# 5-DisplayPort_Ethernet.net
KiCad netlist of a schematic drawn in Altium Designer
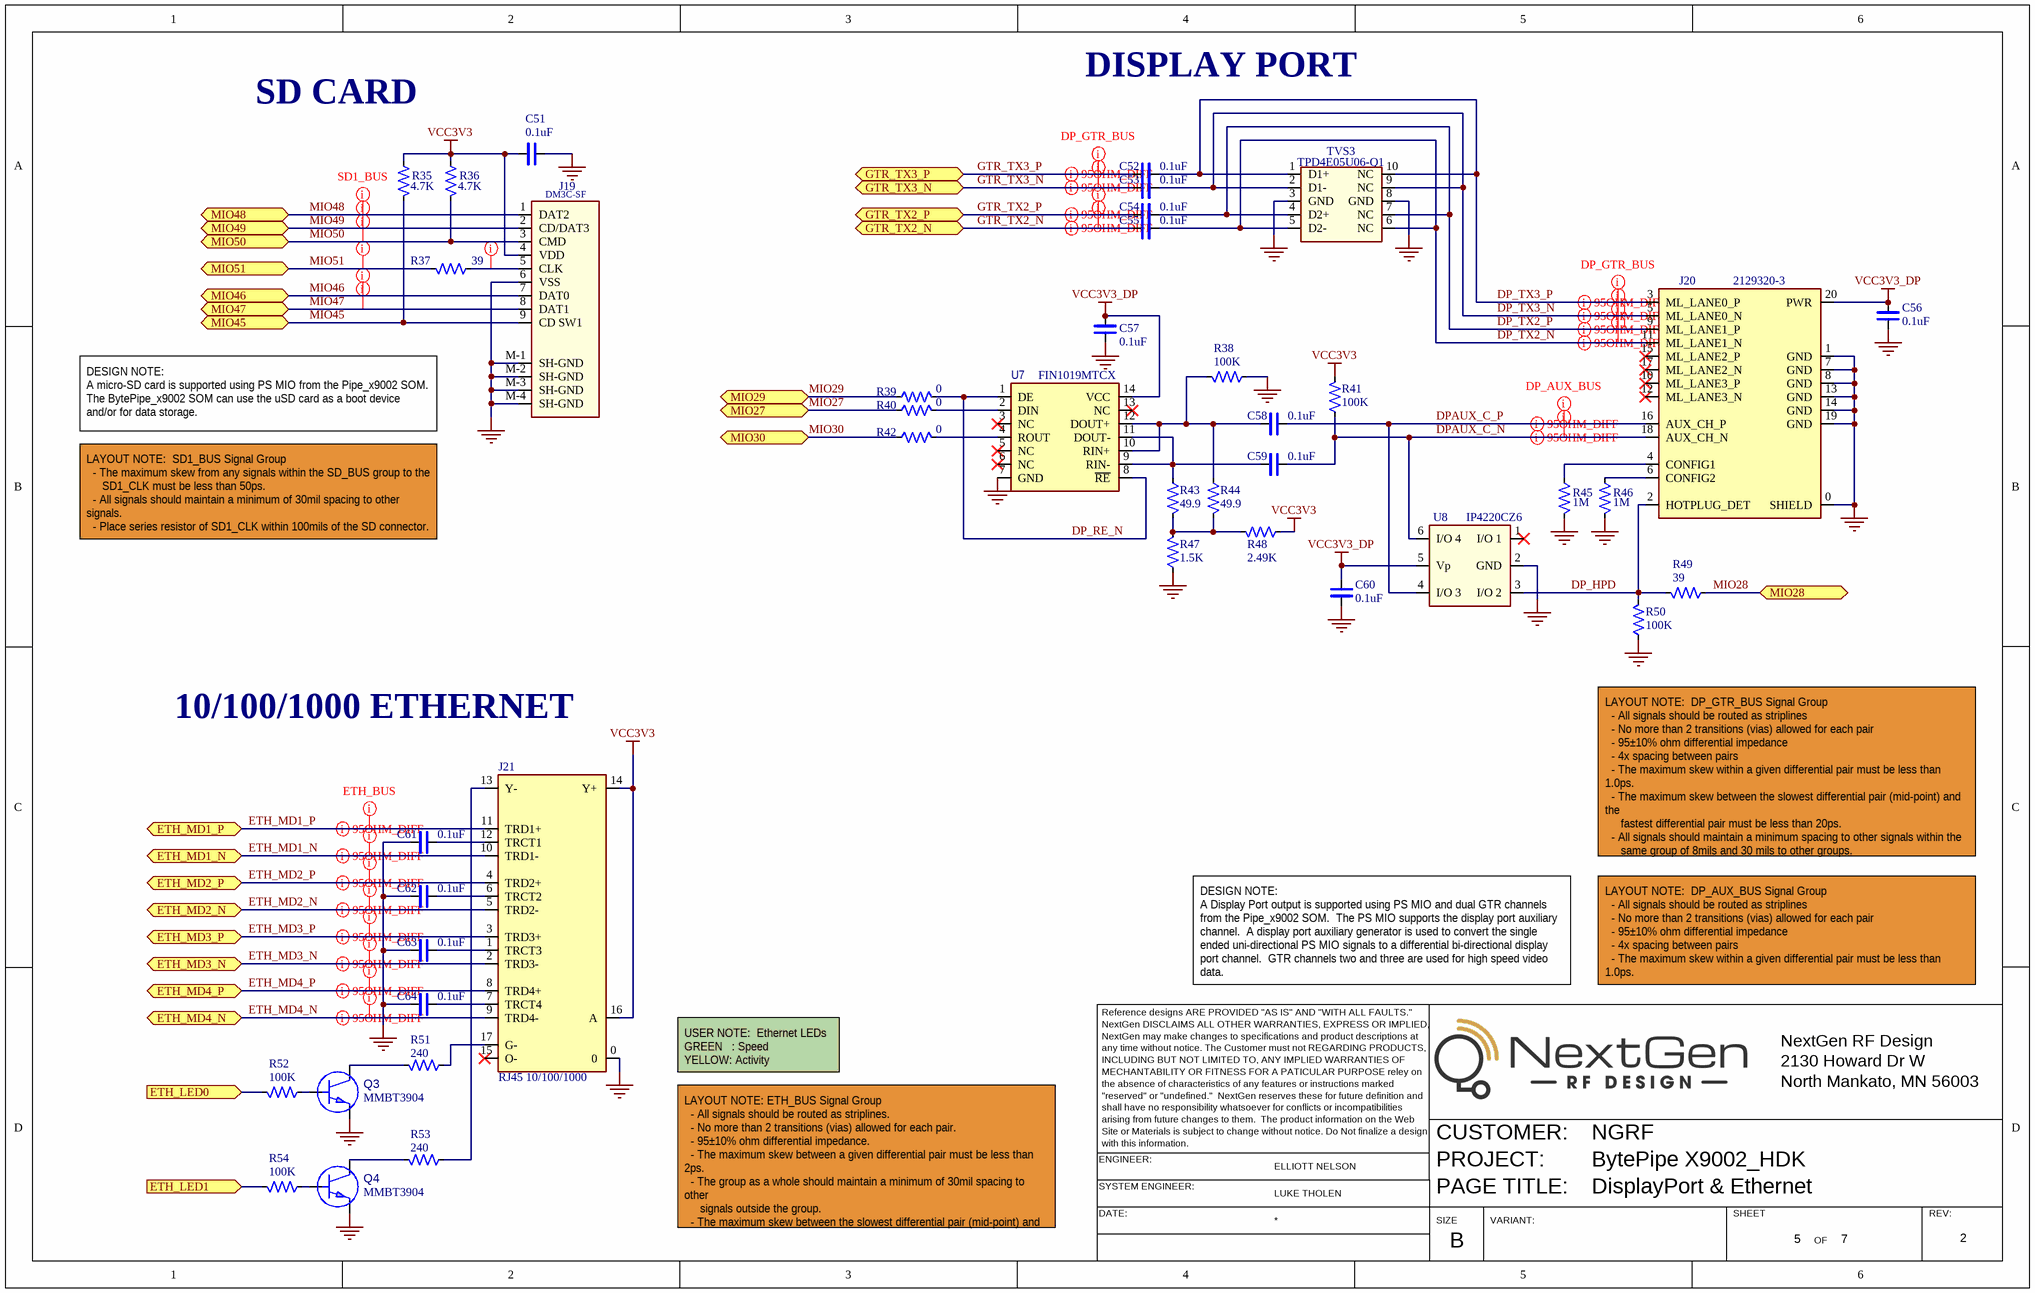
[diagram p0: 5-DisplayPort & Ethernet.SchDoc]

(export (version "E")
  (design (tool "Eeschema 10.0.6"))
  (components
    (comp (ref "C51")
      (value "0.1uF")
      (footprint "SM/0402/CAP")
      (description "CAP CER 0.1UF 25V X7R 0402")
      (fields (field (name "Comment") "CAP_CERAMIC_0402"))
      (libsource (lib "NextGenRF_Symbols_SMT") (part "CAP_CERAMIC_0402"))
    )
    (comp (ref "C52")
      (value "0.1uF")
      (footprint "SM/0402/CAP")
      (description "CAP CER 0.1UF 25V X7R 0402")
      (fields (field (name "Comment") "CAP_CERAMIC_0402"))
      (libsource (lib "NextGenRF_Symbols_SMT") (part "CAP_CERAMIC_0402"))
    )
    (comp (ref "C53")
      (value "0.1uF")
      (footprint "SM/0402/CAP")
      (description "CAP CER 0.1UF 25V X7R 0402")
      (fields (field (name "Comment") "CAP_CERAMIC_0402"))
      (libsource (lib "NextGenRF_Symbols_SMT") (part "CAP_CERAMIC_0402"))
    )
    (comp (ref "C54")
      (value "0.1uF")
      (footprint "SM/0402/CAP")
      (description "CAP CER 0.1UF 25V X7R 0402")
      (fields (field (name "Comment") "CAP_CERAMIC_0402"))
      (libsource (lib "NextGenRF_Symbols_SMT") (part "CAP_CERAMIC_0402"))
    )
    (comp (ref "C55")
      (value "0.1uF")
      (footprint "SM/0402/CAP")
      (description "CAP CER 0.1UF 25V X7R 0402")
      (fields (field (name "Comment") "CAP_CERAMIC_0402"))
      (libsource (lib "NextGenRF_Symbols_SMT") (part "CAP_CERAMIC_0402"))
    )
    (comp (ref "C56")
      (value "0.1uF")
      (footprint "SM/0402/CAP")
      (description "CAP CER 0.1UF 25V X7R 0402")
      (fields (field (name "Comment") "CAP_CERAMIC_0402"))
      (libsource (lib "NextGenRF_Symbols_SMT") (part "CAP_CERAMIC_0402"))
    )
    (comp (ref "C57")
      (value "0.1uF")
      (footprint "SM/0402/CAP")
      (description "CAP CER 0.1UF 25V X7R 0402")
      (fields (field (name "Comment") "CAP_CERAMIC_0402"))
      (libsource (lib "NextGenRF_Symbols_SMT") (part "CAP_CERAMIC_0402"))
    )
    (comp (ref "C58")
      (value "0.1uF")
      (footprint "SM/0402/CAP")
      (description "CAP CER 0.1UF 25V X7R 0402")
      (fields (field (name "Comment") "CAP_CERAMIC_0402"))
      (libsource (lib "NextGenRF_Symbols_SMT") (part "CAP_CERAMIC_0402"))
    )
    (comp (ref "C59")
      (value "0.1uF")
      (footprint "SM/0402/CAP")
      (description "CAP CER 0.1UF 25V X7R 0402")
      (fields (field (name "Comment") "CAP_CERAMIC_0402"))
      (libsource (lib "NextGenRF_Symbols_SMT") (part "CAP_CERAMIC_0402"))
    )
    (comp (ref "C60")
      (value "0.1uF")
      (footprint "SM/0402/CAP")
      (description "CAP CER 0.1UF 25V X7R 0402")
      (fields (field (name "Comment") "CAP_CERAMIC_0402"))
      (libsource (lib "NextGenRF_Symbols_SMT") (part "CAP_CERAMIC_0402"))
    )
    (comp (ref "C61")
      (value "0.1uF")
      (footprint "SM/0402/CAP")
      (description "CAP CER 0.1UF 25V X7R 0402")
      (fields (field (name "Comment") "CAP_CERAMIC_0402"))
      (libsource (lib "NextGenRF_Symbols_SMT") (part "CAP_CERAMIC_0402"))
    )
    (comp (ref "C62")
      (value "0.1uF")
      (footprint "SM/0402/CAP")
      (description "CAP CER 0.1UF 25V X7R 0402")
      (fields (field (name "Comment") "CAP_CERAMIC_0402"))
      (libsource (lib "NextGenRF_Symbols_SMT") (part "CAP_CERAMIC_0402"))
    )
    (comp (ref "C63")
      (value "0.1uF")
      (footprint "SM/0402/CAP")
      (description "CAP CER 0.1UF 25V X7R 0402")
      (fields (field (name "Comment") "CAP_CERAMIC_0402"))
      (libsource (lib "NextGenRF_Symbols_SMT") (part "CAP_CERAMIC_0402"))
    )
    (comp (ref "C64")
      (value "0.1uF")
      (footprint "SM/0402/CAP")
      (description "CAP CER 0.1UF 25V X7R 0402")
      (fields (field (name "Comment") "CAP_CERAMIC_0402"))
      (libsource (lib "NextGenRF_Symbols_SMT") (part "CAP_CERAMIC_0402"))
    )
    (comp (ref "J19")
      (value "DM3C-SF")
      (footprint "SM/CON/MICRO_SD-CARD/HOLDER")
      (description "10 (8 + 2) Position Card Connector Secure Digital - microSD™ Surface Mount, Right Angle Gold")
      (fields (field (name "Comment") "CONN MICRO SD CARD HINGED TYPE"))
      (libsource (lib "NextGenRF_Symbols_SMT") (part "CON_HIROSE_MICRO-SD_HINGED"))
    )
    (comp (ref "J20")
      (value "2129320-3")
      (footprint "CON/TE/2129320-3")
      (description "DisplayPort, Mini  Receptacle Connector 20 Position Through Hole, Right Angle..")
      (fields (field (name "Comment") "CON_TE_2129320-3"))
      (libsource (lib "NextGenRF_Symbols_TH") (part "CON_TE_2129320-3"))
    )
    (comp (ref "J21")
      (value "RJ45 10/100/1000")
      (footprint "CON/RJ45/L829-1J1T-43")
      (description "1 Port RJ45 Magjack Connector Through Hole 10/100/1000 Base-T, AutoMDIX")
      (fields (field (name "Comment") "CON_RJ45_MagJack_L829-1J1T-43"))
      (libsource (lib "NextGenRF_Symbols_TH") (part "CON_RJ45_MagJack_L829-1J1T-43"))
    )
    (comp (ref "Q3")
      (value "MMBT3904")
      (footprint "NGRF_SMT_Footprints:SM/SOT23_A")
      (description "Bipolar (BJT) Transistor NPN 40V 200mA 300MHz 300mW Surface Mount SOT-23-3 (TO-236)")
      (fields (field (name "Comment") "TRANSISTOR_NPN_SOT23"))
      (libsource (lib "NextGenRF_Symbols_SMT") (part "TRANSISTOR_NPN_SOT23"))
    )
    (comp (ref "Q4")
      (value "MMBT3904")
      (footprint "NGRF_SMT_Footprints:SM/SOT23_A")
      (description "Bipolar (BJT) Transistor NPN 40V 200mA 300MHz 300mW Surface Mount SOT-23-3 (TO-236)")
      (fields (field (name "Comment") "TRANSISTOR_NPN_SOT23"))
      (libsource (lib "NextGenRF_Symbols_SMT") (part "TRANSISTOR_NPN_SOT23"))
    )
    (comp (ref "R35")
      (value "4.7K")
      (footprint "SM/0402/RES")
      (description "RES SMD 4.7K OHM 1% 1/10W 0402")
      (fields (field (name "Comment") "RES_0402_A"))
      (libsource (lib "NextGenRF_Symbols_SMT") (part "RES_0402_A"))
    )
    (comp (ref "R36")
      (value "4.7K")
      (footprint "SM/0402/RES")
      (description "RES SMD 4.7K OHM 1% 1/10W 0402")
      (fields (field (name "Comment") "RES_0402_A"))
      (libsource (lib "NextGenRF_Symbols_SMT") (part "RES_0402_A"))
    )
    (comp (ref "R37")
      (value "39")
      (footprint "SM/0402/RES")
      (description "RES SMD 39 OHM 1% 1/10W 0402")
      (fields (field (name "Comment") "RES_0402_A"))
      (libsource (lib "NextGenRF_Symbols_SMT") (part "RES_0402_A"))
    )
    (comp (ref "R38")
      (value "100K")
      (footprint "SM/0402/RES")
      (description "RES SMD 100K OHM 1% 1/10W 0402")
      (fields (field (name "Comment") "RES_0402_A"))
      (libsource (lib "NextGenRF_Symbols_SMT") (part "RES_0402_A"))
    )
    (comp (ref "R39")
      (value "0")
      (footprint "SM/0402/RES")
      (description "RES SMD 0 OHM JUMPER 1/10W 0402")
      (fields (field (name "Comment") "RES_0402_A"))
      (libsource (lib "NextGenRF_Symbols_SMT") (part "RES_0402_A"))
    )
    (comp (ref "R40")
      (value "0")
      (footprint "SM/0402/RES")
      (description "RES SMD 0 OHM JUMPER 1/10W 0402")
      (fields (field (name "Comment") "RES_0402_A"))
      (libsource (lib "NextGenRF_Symbols_SMT") (part "RES_0402_A"))
    )
    (comp (ref "R41")
      (value "100K")
      (footprint "SM/0402/RES")
      (description "RES SMD 100K OHM 1% 1/10W 0402")
      (fields (field (name "Comment") "RES_0402_A"))
      (libsource (lib "NextGenRF_Symbols_SMT") (part "RES_0402_A"))
    )
    (comp (ref "R42")
      (value "0")
      (footprint "SM/0402/RES")
      (description "RES SMD 0 OHM JUMPER 1/10W 0402")
      (fields (field (name "Comment") "RES_0402_A"))
      (libsource (lib "NextGenRF_Symbols_SMT") (part "RES_0402_A"))
    )
    (comp (ref "R43")
      (value "49.9")
      (footprint "SM/0402/RES")
      (description "RES 49.9 OHM 1% 1/10W 0402")
      (fields (field (name "Comment") "RES_0402_A"))
      (libsource (lib "NextGenRF_Symbols_SMT") (part "RES_0402_A"))
    )
    (comp (ref "R44")
      (value "49.9")
      (footprint "SM/0402/RES")
      (description "RES 49.9 OHM 1% 1/10W 0402")
      (fields (field (name "Comment") "RES_0402_A"))
      (libsource (lib "NextGenRF_Symbols_SMT") (part "RES_0402_A"))
    )
    (comp (ref "R45")
      (value "1M")
      (footprint "SM/0402/RES")
      (description "RES SMD 1M OHM 1% 1/10W 0402")
      (fields (field (name "Comment") "RES_0402_A"))
      (libsource (lib "NextGenRF_Symbols_SMT") (part "RES_0402_A"))
    )
    (comp (ref "R46")
      (value "1M")
      (footprint "SM/0402/RES")
      (description "RES SMD 1M OHM 1% 1/10W 0402")
      (fields (field (name "Comment") "RES_0402_A"))
      (libsource (lib "NextGenRF_Symbols_SMT") (part "RES_0402_A"))
    )
    (comp (ref "R47")
      (value "1.5K")
      (footprint "SM/0402/RES")
      (description "RES SMD 1.5K OHM 1% 1/10W 0402")
      (fields (field (name "Comment") "RES_0402_A"))
      (libsource (lib "NextGenRF_Symbols_SMT") (part "RES_0402_A"))
    )
    (comp (ref "R48")
      (value "2.49K")
      (footprint "SM/0402/RES")
      (description "RES SMD 2.49K OHM 1% 1/10W 0402")
      (fields (field (name "Comment") "RES_0402_A"))
      (libsource (lib "NextGenRF_Symbols_SMT") (part "RES_0402_A"))
    )
    (comp (ref "R49")
      (value "39")
      (footprint "SM/0402/RES")
      (description "RES SMD 39 OHM 1% 1/10W 0402")
      (fields (field (name "Comment") "RES_0402_A"))
      (libsource (lib "NextGenRF_Symbols_SMT") (part "RES_0402_A"))
    )
    (comp (ref "R50")
      (value "100K")
      (footprint "SM/0402/RES")
      (description "RES SMD 100K OHM 1% 1/10W 0402")
      (fields (field (name "Comment") "RES_0402_A"))
      (libsource (lib "NextGenRF_Symbols_SMT") (part "RES_0402_A"))
    )
    (comp (ref "R51")
      (value "240")
      (footprint "SM/0402/RES")
      (description "RES SMD 240 OHM 1% 1/10W 0402")
      (fields (field (name "Comment") "RES_0402_A"))
      (libsource (lib "NextGenRF_Symbols_SMT") (part "RES_0402_A"))
    )
    (comp (ref "R52")
      (value "100K")
      (footprint "SM/0402/RES")
      (description "RES SMD 100K OHM 1% 1/10W 0402")
      (fields (field (name "Comment") "RES_0402_A"))
      (libsource (lib "NextGenRF_Symbols_SMT") (part "RES_0402_A"))
    )
    (comp (ref "R53")
      (value "240")
      (footprint "SM/0402/RES")
      (description "RES SMD 240 OHM 1% 1/10W 0402")
      (fields (field (name "Comment") "RES_0402_A"))
      (libsource (lib "NextGenRF_Symbols_SMT") (part "RES_0402_A"))
    )
    (comp (ref "R54")
      (value "100K")
      (footprint "SM/0402/RES")
      (description "RES SMD 100K OHM 1% 1/10W 0402")
      (fields (field (name "Comment") "RES_0402_A"))
      (libsource (lib "NextGenRF_Symbols_SMT") (part "RES_0402_A"))
    )
    (comp (ref "TVS3")
      (value "TPD4E05U06-Q1")
      (footprint "SM/DFN10/2.5X1MM_A")
      (description "TVS DIODE 5.5V 14V 10SON")
      (fields (field (name "Comment") "TVS_TPD4E05U06_2.5mmX1mm"))
      (libsource (lib "NextGenRF_Symbols_SMT") (part "TVS_TPD4E05U06_2.5mmX1mm"))
    )
    (comp (ref "U7")
      (value "FIN1019MTCX")
      (footprint "SM/TSSOP14_5X6.4MM_A")
      (description "1/1 Transceiver Full LVDS 14-TSSOP")
      (fields (field (name "Comment") "IC_FIN1019MTCX_TSSOP-14"))
      (libsource (lib "NextGenRF_Symbols_SMT") (part "IC_FIN1019MTCX_TSSOP-14"))
    )
    (comp (ref "U8")
      (value "IP4220CZ6")
      (footprint "SM/TSOP-6_A")
      (description "Dual USB ESD Protection")
      (fields (field (name "Comment") "IC_IP4220CZ6_TSOP-6"))
      (libsource (lib "NextGenRF_Symbols_SMT") (part "IC_IP4220CZ6_TSOP-6"))
    )
  )
  (nets
    (net (code "1") (name "/DPAUX_C_N") (class "Default")
      (node (ref "C59") (pin "2") (pinfunction "N2_2") (pintype "passive"))
      (node (ref "J20") (pin "18") (pinfunction "AUX_CH_N_18") (pintype "passive"))
      (node (ref "R41") (pin "1") (pinfunction "1_1") (pintype "passive"))
      (node (ref "U8") (pin "6") (pinfunction "I/O_4_6") (pintype "passive"))
    )
    (net (code "2") (name "/DPAUX_C_P") (class "Default")
      (node (ref "C58") (pin "2") (pinfunction "N2_2") (pintype "passive"))
      (node (ref "J20") (pin "16") (pinfunction "AUX_CH_P_16") (pintype "passive"))
      (node (ref "U8") (pin "4") (pinfunction "I/O_3_4") (pintype "passive"))
    )
    (net (code "3") (name "/DP_HPD") (class "Default")
      (node (ref "J20") (pin "2") (pinfunction "HOTPLUG_DET_2") (pintype "passive"))
      (node (ref "R49") (pin "2") (pinfunction "2_2") (pintype "passive"))
      (node (ref "R50") (pin "2") (pinfunction "2_2") (pintype "passive"))
      (node (ref "U8") (pin "3") (pinfunction "I/O_2_3") (pintype "passive"))
    )
    (net (code "4") (name "/DP_RE_N") (class "Default")
      (node (ref "R39") (pin "1") (pinfunction "1_1") (pintype "passive"))
      (node (ref "U7") (pin "1") (pinfunction "DE_1") (pintype "passive"))
      (node (ref "U7") (pin "8") (pinfunction "~{RE}_8") (pintype "passive"))
    )
    (net (code "5") (name "/DP_TX2_N") (class "Default")
      (node (ref "C55") (pin "2") (pinfunction "N2_2") (pintype "passive"))
      (node (ref "J20") (pin "11") (pinfunction "ML_LANE1_N_11") (pintype "passive"))
      (node (ref "TVS3") (pin "5") (pinfunction "D2-_5") (pintype "passive"))
      (node (ref "TVS3") (pin "6") (pinfunction "NC_6") (pintype "passive"))
    )
    (net (code "6") (name "/DP_TX2_P") (class "Default")
      (node (ref "C54") (pin "2") (pinfunction "N2_2") (pintype "passive"))
      (node (ref "J20") (pin "9") (pinfunction "ML_LANE1_P_9") (pintype "passive"))
      (node (ref "TVS3") (pin "4") (pinfunction "D2+_4") (pintype "passive"))
      (node (ref "TVS3") (pin "7") (pinfunction "NC_7") (pintype "passive"))
    )
    (net (code "7") (name "/DP_TX3_N") (class "Default")
      (node (ref "C53") (pin "2") (pinfunction "N2_2") (pintype "passive"))
      (node (ref "J20") (pin "5") (pinfunction "ML_LANE0_N_5") (pintype "passive"))
      (node (ref "TVS3") (pin "2") (pinfunction "D1-_2") (pintype "passive"))
      (node (ref "TVS3") (pin "9") (pinfunction "NC_9") (pintype "passive"))
    )
    (net (code "8") (name "/DP_TX3_P") (class "Default")
      (node (ref "C52") (pin "2") (pinfunction "N2_2") (pintype "passive"))
      (node (ref "J20") (pin "3") (pinfunction "ML_LANE0_P_3") (pintype "passive"))
      (node (ref "TVS3") (pin "1") (pinfunction "D1+_1") (pintype "passive"))
      (node (ref "TVS3") (pin "10") (pinfunction "NC_10") (pintype "passive"))
    )
    (net (code "9") (name "/ETH_LED0") (class "Default")
      (node (ref "R52") (pin "2") (pinfunction "2_2") (pintype "passive"))
    )
    (net (code "10") (name "/ETH_LED1") (class "Default")
      (node (ref "R54") (pin "2") (pinfunction "2_2") (pintype "passive"))
    )
    (net (code "11") (name "/ETH_MD1_N") (class "Default")
      (node (ref "J21") (pin "10") (pinfunction "TRD1-_10") (pintype "passive"))
    )
    (net (code "12") (name "/ETH_MD1_P") (class "Default")
      (node (ref "J21") (pin "11") (pinfunction "TRD1+_11") (pintype "passive"))
    )
    (net (code "13") (name "/ETH_MD2_N") (class "Default")
      (node (ref "J21") (pin "5") (pinfunction "TRD2-_5") (pintype "passive"))
    )
    (net (code "14") (name "/ETH_MD2_P") (class "Default")
      (node (ref "J21") (pin "4") (pinfunction "TRD2+_4") (pintype "passive"))
    )
    (net (code "15") (name "/ETH_MD3_N") (class "Default")
      (node (ref "J21") (pin "2") (pinfunction "TRD3-_2") (pintype "passive"))
    )
    (net (code "16") (name "/ETH_MD3_P") (class "Default")
      (node (ref "J21") (pin "3") (pinfunction "TRD3+_3") (pintype "passive"))
    )
    (net (code "17") (name "/ETH_MD4_N") (class "Default")
      (node (ref "J21") (pin "9") (pinfunction "TRD4-_9") (pintype "passive"))
    )
    (net (code "18") (name "/ETH_MD4_P") (class "Default")
      (node (ref "J21") (pin "8") (pinfunction "TRD4+_8") (pintype "passive"))
    )
    (net (code "19") (name "/GTR_TX2_N") (class "Default")
      (node (ref "C55") (pin "1") (pinfunction "N1_1") (pintype "passive"))
    )
    (net (code "20") (name "/GTR_TX2_P") (class "Default")
      (node (ref "C54") (pin "1") (pinfunction "N1_1") (pintype "passive"))
    )
    (net (code "21") (name "/GTR_TX3_N") (class "Default")
      (node (ref "C53") (pin "1") (pinfunction "N1_1") (pintype "passive"))
    )
    (net (code "22") (name "/GTR_TX3_P") (class "Default")
      (node (ref "C52") (pin "1") (pinfunction "N1_1") (pintype "passive"))
    )
    (net (code "23") (name "/MIO27") (class "Default")
      (node (ref "R40") (pin "2") (pinfunction "2_2") (pintype "passive"))
    )
    (net (code "24") (name "/MIO28") (class "Default")
      (node (ref "R49") (pin "1") (pinfunction "1_1") (pintype "passive"))
    )
    (net (code "25") (name "/MIO29") (class "Default")
      (node (ref "R39") (pin "2") (pinfunction "2_2") (pintype "passive"))
    )
    (net (code "26") (name "/MIO30") (class "Default")
      (node (ref "R42") (pin "2") (pinfunction "2_2") (pintype "passive"))
    )
    (net (code "27") (name "/MIO45") (class "Default")
      (node (ref "J19") (pin "9") (pinfunction "CD_SW1_9") (pintype "passive"))
      (node (ref "R35") (pin "2") (pinfunction "2_2") (pintype "passive"))
    )
    (net (code "28") (name "/MIO46") (class "Default")
      (node (ref "J19") (pin "7") (pinfunction "DAT0_7") (pintype "passive"))
    )
    (net (code "29") (name "/MIO47") (class "Default")
      (node (ref "J19") (pin "8") (pinfunction "DAT1_8") (pintype "passive"))
    )
    (net (code "30") (name "/MIO48") (class "Default")
      (node (ref "J19") (pin "1") (pinfunction "DAT2_1") (pintype "passive"))
    )
    (net (code "31") (name "/MIO49") (class "Default")
      (node (ref "J19") (pin "2") (pinfunction "CD/DAT3_2") (pintype "passive"))
    )
    (net (code "32") (name "/MIO50") (class "Default")
      (node (ref "J19") (pin "3") (pinfunction "CMD_3") (pintype "passive"))
      (node (ref "R36") (pin "2") (pinfunction "2_2") (pintype "passive"))
    )
    (net (code "33") (name "/MIO51") (class "Default")
      (node (ref "R37") (pin "2") (pinfunction "2_2") (pintype "passive"))
    )
    (net (code "34") (name "GND") (class "Default")
      (node (ref "C51") (pin "2") (pinfunction "N2_2") (pintype "passive"))
      (node (ref "C56") (pin "2") (pinfunction "N2_2") (pintype "passive"))
      (node (ref "C57") (pin "2") (pinfunction "N2_2") (pintype "passive"))
      (node (ref "C60") (pin "2") (pinfunction "N2_2") (pintype "passive"))
      (node (ref "C61") (pin "1") (pinfunction "N1_1") (pintype "passive"))
      (node (ref "C62") (pin "1") (pinfunction "N1_1") (pintype "passive"))
      (node (ref "C63") (pin "1") (pinfunction "N1_1") (pintype "passive"))
      (node (ref "C64") (pin "1") (pinfunction "N1_1") (pintype "passive"))
      (node (ref "J19") (pin "6") (pinfunction "VSS_6") (pintype "passive"))
      (node (ref "J19") (pin "M-1") (pinfunction "SH-GND_M-1") (pintype "passive"))
      (node (ref "J19") (pin "M-2") (pinfunction "SH-GND_M-2") (pintype "passive"))
      (node (ref "J19") (pin "M-3") (pinfunction "SH-GND_M-3") (pintype "passive"))
      (node (ref "J19") (pin "M-4") (pinfunction "SH-GND_M-4") (pintype "passive"))
      (node (ref "J20") (pin "0") (pinfunction "SHIELD_0") (pintype "passive"))
      (node (ref "J20") (pin "1") (pinfunction "GND_1") (pintype "passive"))
      (node (ref "J20") (pin "13") (pinfunction "GND_13") (pintype "passive"))
      (node (ref "J20") (pin "14") (pinfunction "GND_14") (pintype "passive"))
      (node (ref "J20") (pin "19") (pinfunction "GND_19") (pintype "passive"))
      (node (ref "J20") (pin "7") (pinfunction "GND_7") (pintype "passive"))
      (node (ref "J20") (pin "8") (pinfunction "GND_8") (pintype "passive"))
      (node (ref "J21") (pin "0") (pinfunction "0_0") (pintype "passive"))
      (node (ref "Q3") (pin "2") (pinfunction "E_2") (pintype "passive"))
      (node (ref "Q4") (pin "2") (pinfunction "E_2") (pintype "passive"))
      (node (ref "R38") (pin "1") (pinfunction "1_1") (pintype "passive"))
      (node (ref "R45") (pin "2") (pinfunction "2_2") (pintype "passive"))
      (node (ref "R46") (pin "2") (pinfunction "2_2") (pintype "passive"))
      (node (ref "R47") (pin "1") (pinfunction "1_1") (pintype "passive"))
      (node (ref "R50") (pin "1") (pinfunction "1_1") (pintype "passive"))
      (node (ref "TVS3") (pin "3") (pinfunction "GND_3") (pintype "passive"))
      (node (ref "TVS3") (pin "8") (pinfunction "GND_8") (pintype "passive"))
      (node (ref "U7") (pin "7") (pinfunction "GND_7") (pintype "passive"))
      (node (ref "U8") (pin "2") (pinfunction "GND_2") (pintype "passive"))
    )
    (net (code "35") (name "Net-(C58-N1)") (class "Default")
      (node (ref "C58") (pin "1") (pinfunction "N1_1") (pintype "passive"))
      (node (ref "R38") (pin "2") (pinfunction "2_2") (pintype "passive"))
      (node (ref "R44") (pin "1") (pinfunction "1_1") (pintype "passive"))
      (node (ref "U7") (pin "10") (pinfunction "RIN+_10") (pintype "passive"))
      (node (ref "U7") (pin "12") (pinfunction "DOUT+_12") (pintype "passive"))
    )
    (net (code "36") (name "Net-(C59-N1)") (class "Default")
      (node (ref "C59") (pin "1") (pinfunction "N1_1") (pintype "passive"))
      (node (ref "R43") (pin "1") (pinfunction "1_1") (pintype "passive"))
      (node (ref "U7") (pin "11") (pinfunction "DOUT-_11") (pintype "passive"))
      (node (ref "U7") (pin "9") (pinfunction "RIN-_9") (pintype "passive"))
    )
    (net (code "37") (name "Net-(C61-N2)") (class "Default")
      (node (ref "C61") (pin "2") (pinfunction "N2_2") (pintype "passive"))
      (node (ref "J21") (pin "12") (pinfunction "TRCT1_12") (pintype "passive"))
    )
    (net (code "38") (name "Net-(C62-N2)") (class "Default")
      (node (ref "C62") (pin "2") (pinfunction "N2_2") (pintype "passive"))
      (node (ref "J21") (pin "6") (pinfunction "TRCT2_6") (pintype "passive"))
    )
    (net (code "39") (name "Net-(C63-N2)") (class "Default")
      (node (ref "C63") (pin "2") (pinfunction "N2_2") (pintype "passive"))
      (node (ref "J21") (pin "1") (pinfunction "TRCT3_1") (pintype "passive"))
    )
    (net (code "40") (name "Net-(C64-N2)") (class "Default")
      (node (ref "C64") (pin "2") (pinfunction "N2_2") (pintype "passive"))
      (node (ref "J21") (pin "7") (pinfunction "TRCT4_7") (pintype "passive"))
    )
    (net (code "41") (name "Net-(J19-CLK)") (class "Default")
      (node (ref "J19") (pin "5") (pinfunction "CLK_5") (pintype "passive"))
      (node (ref "R37") (pin "1") (pinfunction "1_1") (pintype "passive"))
    )
    (net (code "42") (name "Net-(J20-CONFIG1)") (class "Default")
      (node (ref "J20") (pin "4") (pinfunction "CONFIG1_4") (pintype "passive"))
      (node (ref "R45") (pin "1") (pinfunction "1_1") (pintype "passive"))
    )
    (net (code "43") (name "Net-(J20-CONFIG2)") (class "Default")
      (node (ref "J20") (pin "6") (pinfunction "CONFIG2_6") (pintype "passive"))
      (node (ref "R46") (pin "1") (pinfunction "1_1") (pintype "passive"))
    )
    (net (code "44") (name "Net-(J21-G-)") (class "Default")
      (node (ref "J21") (pin "17") (pinfunction "G-_17") (pintype "passive"))
      (node (ref "R51") (pin "2") (pinfunction "2_2") (pintype "passive"))
    )
    (net (code "45") (name "Net-(J21-Y-)") (class "Default")
      (node (ref "J21") (pin "13") (pinfunction "Y-_13") (pintype "passive"))
      (node (ref "R53") (pin "2") (pinfunction "2_2") (pintype "passive"))
    )
    (net (code "46") (name "Net-(Q3-B)") (class "Default")
      (node (ref "Q3") (pin "1") (pinfunction "B_1") (pintype "passive"))
      (node (ref "R52") (pin "1") (pinfunction "1_1") (pintype "passive"))
    )
    (net (code "47") (name "Net-(Q3-C)") (class "Default")
      (node (ref "Q3") (pin "3") (pinfunction "C_3") (pintype "passive"))
      (node (ref "R51") (pin "1") (pinfunction "1_1") (pintype "passive"))
    )
    (net (code "48") (name "Net-(Q4-B)") (class "Default")
      (node (ref "Q4") (pin "1") (pinfunction "B_1") (pintype "passive"))
      (node (ref "R54") (pin "1") (pinfunction "1_1") (pintype "passive"))
    )
    (net (code "49") (name "Net-(Q4-C)") (class "Default")
      (node (ref "Q4") (pin "3") (pinfunction "C_3") (pintype "passive"))
      (node (ref "R53") (pin "1") (pinfunction "1_1") (pintype "passive"))
    )
    (net (code "50") (name "Net-(R43-Pad2)") (class "Default")
      (node (ref "R43") (pin "2") (pinfunction "2_2") (pintype "passive"))
      (node (ref "R44") (pin "2") (pinfunction "2_2") (pintype "passive"))
      (node (ref "R47") (pin "2") (pinfunction "2_2") (pintype "passive"))
      (node (ref "R48") (pin "2") (pinfunction "2_2") (pintype "passive"))
    )
    (net (code "51") (name "Net-(U7-DIN)") (class "Default")
      (node (ref "R40") (pin "1") (pinfunction "1_1") (pintype "passive"))
      (node (ref "U7") (pin "2") (pinfunction "DIN_2") (pintype "passive"))
    )
    (net (code "52") (name "Net-(U7-ROUT)") (class "Default")
      (node (ref "R42") (pin "1") (pinfunction "1_1") (pintype "passive"))
      (node (ref "U7") (pin "4") (pinfunction "ROUT_4") (pintype "passive"))
    )
    (net (code "53") (name "VCC3V3") (class "Default")
      (node (ref "C51") (pin "1") (pinfunction "N1_1") (pintype "passive"))
      (node (ref "J19") (pin "4") (pinfunction "VDD_4") (pintype "passive"))
      (node (ref "J21") (pin "14") (pinfunction "Y+_14") (pintype "passive"))
      (node (ref "J21") (pin "16") (pinfunction "A_16") (pintype "passive"))
      (node (ref "R35") (pin "1") (pinfunction "1_1") (pintype "passive"))
      (node (ref "R36") (pin "1") (pinfunction "1_1") (pintype "passive"))
      (node (ref "R41") (pin "2") (pinfunction "2_2") (pintype "passive"))
      (node (ref "R48") (pin "1") (pinfunction "1_1") (pintype "passive"))
    )
    (net (code "54") (name "VCC3V3_DP") (class "Default")
      (node (ref "C56") (pin "1") (pinfunction "N1_1") (pintype "passive"))
      (node (ref "C57") (pin "1") (pinfunction "N1_1") (pintype "passive"))
      (node (ref "C60") (pin "1") (pinfunction "N1_1") (pintype "passive"))
      (node (ref "J20") (pin "20") (pinfunction "PWR_20") (pintype "passive"))
      (node (ref "U7") (pin "14") (pinfunction "VCC_14") (pintype "passive"))
      (node (ref "U8") (pin "5") (pinfunction "Vp_5") (pintype "passive"))
    )
    (net (code "55") (name "unconnected-(J20-ML_LANE2_N-Pad17)") (class "Default")
      (node (ref "J20") (pin "17") (pinfunction "ML_LANE2_N_17") (pintype "passive+no_connect"))
    )
    (net (code "56") (name "unconnected-(J20-ML_LANE2_P-Pad15)") (class "Default")
      (node (ref "J20") (pin "15") (pinfunction "ML_LANE2_P_15") (pintype "passive+no_connect"))
    )
    (net (code "57") (name "unconnected-(J20-ML_LANE3_N-Pad12)") (class "Default")
      (node (ref "J20") (pin "12") (pinfunction "ML_LANE3_N_12") (pintype "passive+no_connect"))
    )
    (net (code "58") (name "unconnected-(J20-ML_LANE3_P-Pad10)") (class "Default")
      (node (ref "J20") (pin "10") (pinfunction "ML_LANE3_P_10") (pintype "passive+no_connect"))
    )
    (net (code "59") (name "unconnected-(J21-O--Pad15)") (class "Default")
      (node (ref "J21") (pin "15") (pinfunction "O-_15") (pintype "passive+no_connect"))
    )
    (net (code "60") (name "unconnected-(U7-NC-Pad3)") (class "Default")
      (node (ref "U7") (pin "3") (pinfunction "NC_3") (pintype "passive+no_connect"))
    )
    (net (code "61") (name "unconnected-(U7-NC-Pad5)") (class "Default")
      (node (ref "U7") (pin "5") (pinfunction "NC_5") (pintype "passive+no_connect"))
    )
    (net (code "62") (name "unconnected-(U7-NC-Pad6)") (class "Default")
      (node (ref "U7") (pin "6") (pinfunction "NC_6") (pintype "passive+no_connect"))
    )
    (net (code "63") (name "unconnected-(U7-NC-Pad13)") (class "Default")
      (node (ref "U7") (pin "13") (pinfunction "NC_13") (pintype "passive+no_connect"))
    )
    (net (code "64") (name "unconnected-(U8-I{slash}O_1-Pad1)") (class "Default")
      (node (ref "U8") (pin "1") (pinfunction "I/O_1_1") (pintype "passive+no_connect"))
    )
  )
)
